# T07_411.net
KiCad netlist of a schematic drawn in EAGLE
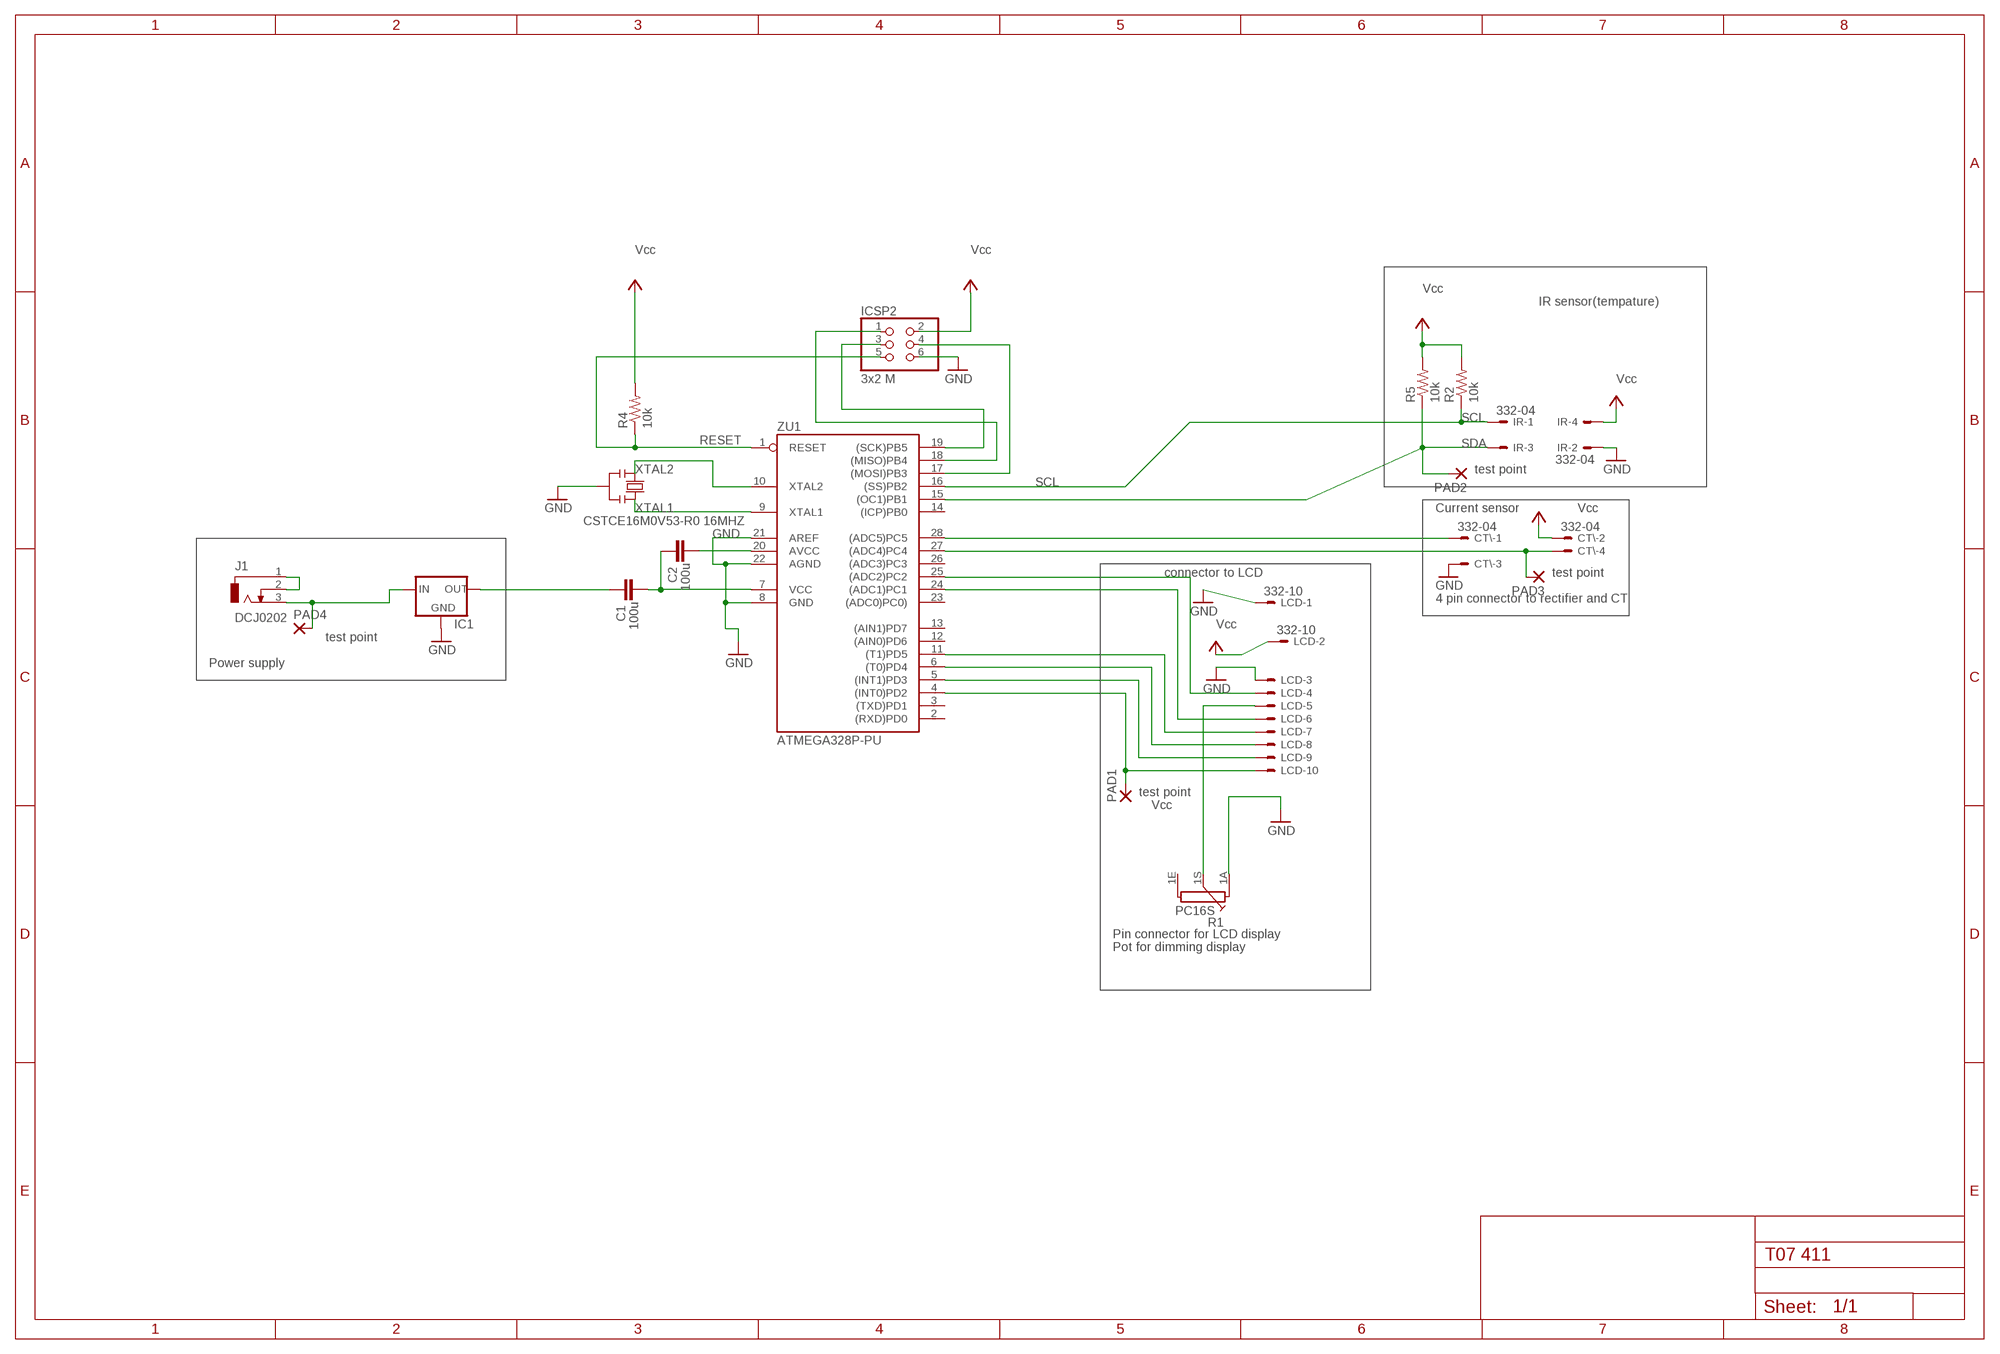
[diagram p0: schematic, sheet 1]

(export (version "E")
  (design (tool "Eeschema 10.0.6"))
  (components
    (comp (ref "C1")
      (value "100u")
      (footprint "eagle-import:C0603-ROUND")
      (libsource (lib "eagle-import") (part "C-EU0603-RND"))
    )
    (comp (ref "C2")
      (value "100u")
      (footprint "eagle-import:C0603-ROUND")
      (libsource (lib "eagle-import") (part "C-EU0603-RND"))
    )
    (comp (ref "CT\\")
      (value "332-04")
      (footprint "eagle-import:332-04")
      (libsource (lib "eagle-import") (part "332-04"))
    )
    (comp (ref "IC1")
      (value "78XXL")
      (footprint "eagle-import:78XXL")
      (libsource (lib "eagle-import") (part "78XXL"))
    )
    (comp (ref "ICSP2")
      (value "3x2 M")
      (footprint "eagle-import:2X03")
      (libsource (lib "eagle-import") (part "PINHD-2X3"))
    )
    (comp (ref "IR")
      (value "332-04")
      (footprint "eagle-import:332-04")
      (libsource (lib "eagle-import") (part "332-04"))
    )
    (comp (ref "J1")
      (value "DCJ0202")
      (footprint "eagle-import:DCJ0202")
      (libsource (lib "eagle-import") (part "DCJ0202"))
    )
    (comp (ref "LCD")
      (value "332-10")
      (footprint "eagle-import:332-10")
      (libsource (lib "eagle-import") (part "332-10"))
    )
    (comp (ref "PAD1")
      (value "1,6/0,9")
      (footprint "eagle-import:1,6_0,9")
      (libsource (lib "eagle-import") (part "1,6/0,9"))
    )
    (comp (ref "PAD2")
      (value "1,6/0,9")
      (footprint "eagle-import:1,6_0,9")
      (libsource (lib "eagle-import") (part "1,6/0,9"))
    )
    (comp (ref "PAD3")
      (value "1,6/0,9")
      (footprint "eagle-import:1,6_0,9")
      (libsource (lib "eagle-import") (part "1,6/0,9"))
    )
    (comp (ref "PAD4")
      (value "1,6/0,9")
      (footprint "eagle-import:1,6_0,9")
      (libsource (lib "eagle-import") (part "1,6/0,9"))
    )
    (comp (ref "R1")
      (value "PC16S")
      (footprint "eagle-import:PC16S")
      (libsource (lib "eagle-import") (part "PC16S"))
    )
    (comp (ref "R2")
      (value "10k")
      (footprint "eagle-import:0402-RES")
      (libsource (lib "eagle-import") (part "RESISTOR0402-RES"))
    )
    (comp (ref "R4")
      (value "10k")
      (footprint "eagle-import:0402-RES")
      (libsource (lib "eagle-import") (part "RESISTOR0402-RES"))
    )
    (comp (ref "R5")
      (value "10k")
      (footprint "eagle-import:0402-RES")
      (libsource (lib "eagle-import") (part "RESISTOR0402-RES"))
    )
    (comp (ref "Y3")
      (value "CSTCE16M0V53-R0 16MHZ")
      (footprint "eagle-import:RESONATOR")
      (libsource (lib "eagle-import") (part "RESONATORMU"))
    )
    (comp (ref "ZU1")
      (value "ATMEGA328P-PU")
      (footprint "eagle-import:DIL28-3")
      (libsource (lib "eagle-import") (part "ATMEGA328P-PU"))
    )
  )
  (nets
    (net (code "1") (name "+5V") (class "Default")
      (node (ref "CT\\") (pin "2") (pinfunction "S_2") (pintype "passive"))
      (node (ref "ICSP2") (pin "2") (pinfunction "2_2") (pintype "passive"))
      (node (ref "IR") (pin "4") (pinfunction "S_4") (pintype "passive"))
      (node (ref "LCD") (pin "2") (pinfunction "S_2") (pintype "passive"))
      (node (ref "R2") (pin "2") (pinfunction "2_2") (pintype "passive"))
      (node (ref "R4") (pin "2") (pinfunction "2_2") (pintype "passive"))
      (node (ref "R5") (pin "2") (pinfunction "2_2") (pintype "passive"))
    )
    (net (code "2") (name "/RESET") (class "Default")
      (node (ref "ICSP2") (pin "5") (pinfunction "5_5") (pintype "passive"))
      (node (ref "R4") (pin "1") (pinfunction "1_1") (pintype "passive"))
      (node (ref "ZU1") (pin "1") (pinfunction "RESET_1") (pintype "input"))
    )
    (net (code "3") (name "/SCL") (class "Default")
      (node (ref "IR") (pin "1") (pinfunction "S_1") (pintype "passive"))
      (node (ref "R2") (pin "1") (pinfunction "1_1") (pintype "passive"))
      (node (ref "ZU1") (pin "16") (pinfunction "(SS)PB2_16") (pintype "bidirectional"))
    )
    (net (code "4") (name "/SDA") (class "Default")
      (node (ref "IR") (pin "3") (pinfunction "S_3") (pintype "passive"))
      (node (ref "PAD2") (pin "1") (pinfunction "P_1") (pintype "passive"))
      (node (ref "R5") (pin "1") (pinfunction "1_1") (pintype "passive"))
      (node (ref "ZU1") (pin "15") (pinfunction "(OC1)PB1_15") (pintype "bidirectional"))
    )
    (net (code "5") (name "/XTAL1") (class "Default")
      (node (ref "Y3") (pin "3") (pinfunction "3_3") (pintype "passive"))
      (node (ref "ZU1") (pin "9") (pinfunction "XTAL1_9") (pintype "bidirectional"))
    )
    (net (code "6") (name "/XTAL2") (class "Default")
      (node (ref "Y3") (pin "1") (pinfunction "1_1") (pintype "passive"))
      (node (ref "ZU1") (pin "10") (pinfunction "XTAL2_10") (pintype "bidirectional"))
    )
    (net (code "7") (name "GND") (class "Default")
      (node (ref "CT\\") (pin "3") (pinfunction "S_3") (pintype "passive"))
      (node (ref "IC1") (pin "GND") (pinfunction "GND_GND") (pintype "input"))
      (node (ref "ICSP2") (pin "6") (pinfunction "6_6") (pintype "passive"))
      (node (ref "IR") (pin "2") (pinfunction "S_2") (pintype "passive"))
      (node (ref "LCD") (pin "1") (pinfunction "S_1") (pintype "passive"))
      (node (ref "LCD") (pin "3") (pinfunction "S_3") (pintype "passive"))
      (node (ref "R1") (pin "1A") (pinfunction "1A_1A") (pintype "passive"))
      (node (ref "Y3") (pin "2") (pinfunction "2_2") (pintype "passive"))
      (node (ref "ZU1") (pin "21") (pinfunction "AREF_21") (pintype "passive"))
      (node (ref "ZU1") (pin "22") (pinfunction "AGND_22") (pintype "power_in"))
      (node (ref "ZU1") (pin "8") (pinfunction "GND_8") (pintype "power_in"))
    )
    (net (code "8") (name "Net-(C1-Pad2)") (class "Default")
      (node (ref "C1") (pin "2") (pinfunction "2_2") (pintype "passive"))
      (node (ref "IC1") (pin "OUT") (pinfunction "OUT_OUT") (pintype "passive"))
    )
    (net (code "9") (name "Net-(CT\\A-S)") (class "Default")
      (node (ref "CT\\") (pin "1") (pinfunction "S_1") (pintype "passive"))
      (node (ref "ZU1") (pin "28") (pinfunction "(ADC5)PC5_28") (pintype "bidirectional"))
    )
    (net (code "10") (name "Net-(CT\\D-S)") (class "Default")
      (node (ref "CT\\") (pin "4") (pinfunction "S_4") (pintype "passive"))
      (node (ref "PAD3") (pin "1") (pinfunction "P_1") (pintype "passive"))
      (node (ref "ZU1") (pin "27") (pinfunction "(ADC4)PC4_27") (pintype "bidirectional"))
    )
    (net (code "11") (name "Net-(J1-Pad1)") (class "Default")
      (node (ref "J1") (pin "1") (pinfunction "1_1") (pintype "passive"))
      (node (ref "J1") (pin "2") (pinfunction "2_2") (pintype "passive"))
    )
    (net (code "12") (name "Net-(LCDB-S)") (class "Default")
      (node (ref "LCD") (pin "10") (pinfunction "S_10") (pintype "passive"))
      (node (ref "PAD1") (pin "1") (pinfunction "P_1") (pintype "passive"))
      (node (ref "ZU1") (pin "4") (pinfunction "(INT0)PD2_4") (pintype "bidirectional"))
    )
    (net (code "13") (name "Net-(LCDE-S)") (class "Default")
      (node (ref "LCD") (pin "4") (pinfunction "S_4") (pintype "passive"))
      (node (ref "ZU1") (pin "25") (pinfunction "(ADC2)PC2_25") (pintype "bidirectional"))
    )
    (net (code "14") (name "Net-(LCDF-S)") (class "Default")
      (node (ref "LCD") (pin "5") (pinfunction "S_5") (pintype "passive"))
      (node (ref "R1") (pin "1S") (pinfunction "1S_1S") (pintype "passive"))
    )
    (net (code "15") (name "Net-(LCDG-S)") (class "Default")
      (node (ref "LCD") (pin "6") (pinfunction "S_6") (pintype "passive"))
      (node (ref "ZU1") (pin "24") (pinfunction "(ADC1)PC1_24") (pintype "bidirectional"))
    )
    (net (code "16") (name "Net-(LCDH-S)") (class "Default")
      (node (ref "LCD") (pin "7") (pinfunction "S_7") (pintype "passive"))
      (node (ref "ZU1") (pin "11") (pinfunction "(T1)PD5_11") (pintype "bidirectional"))
    )
    (net (code "17") (name "Net-(LCDI-S)") (class "Default")
      (node (ref "LCD") (pin "8") (pinfunction "S_8") (pintype "passive"))
      (node (ref "ZU1") (pin "6") (pinfunction "(T0)PD4_6") (pintype "bidirectional"))
    )
    (net (code "18") (name "Net-(LCDJ-S)") (class "Default")
      (node (ref "LCD") (pin "9") (pinfunction "S_9") (pintype "passive"))
      (node (ref "ZU1") (pin "5") (pinfunction "(INT1)PD3_5") (pintype "bidirectional"))
    )
    (net (code "19") (name "Net-(PAD4-P)") (class "Default")
      (node (ref "IC1") (pin "IN") (pinfunction "IN_IN") (pintype "input"))
      (node (ref "J1") (pin "3") (pinfunction "3_3") (pintype "passive"))
      (node (ref "PAD4") (pin "1") (pinfunction "P_1") (pintype "passive"))
    )
    (net (code "20") (name "Net-(ZU1-(MISO)PB4)") (class "Default")
      (node (ref "ICSP2") (pin "1") (pinfunction "1_1") (pintype "passive"))
      (node (ref "ZU1") (pin "18") (pinfunction "(MISO)PB4_18") (pintype "bidirectional"))
    )
    (net (code "21") (name "Net-(ZU1-(MOSI)PB3)") (class "Default")
      (node (ref "ICSP2") (pin "4") (pinfunction "4_4") (pintype "passive"))
      (node (ref "ZU1") (pin "17") (pinfunction "(MOSI)PB3_17") (pintype "bidirectional"))
    )
    (net (code "22") (name "Net-(ZU1-(SCK)PB5)") (class "Default")
      (node (ref "ICSP2") (pin "3") (pinfunction "3_3") (pintype "passive"))
      (node (ref "ZU1") (pin "19") (pinfunction "(SCK)PB5_19") (pintype "bidirectional"))
    )
    (net (code "23") (name "Net-(ZU1-AVCC)") (class "Default")
      (node (ref "C2") (pin "1") (pinfunction "1_1") (pintype "passive"))
      (node (ref "ZU1") (pin "20") (pinfunction "AVCC_20") (pintype "power_in"))
    )
    (net (code "24") (name "Net-(ZU1-VCC)") (class "Default")
      (node (ref "C1") (pin "1") (pinfunction "1_1") (pintype "passive"))
      (node (ref "C2") (pin "2") (pinfunction "2_2") (pintype "passive"))
      (node (ref "ZU1") (pin "7") (pinfunction "VCC_7") (pintype "power_in"))
    )
    (net (code "25") (name "unconnected-(R1-Pad1E)") (class "Default")
      (node (ref "R1") (pin "1E") (pinfunction "1E_1E") (pintype "passive"))
    )
    (net (code "26") (name "unconnected-(ZU1-(ADC0)PC0)-Pad23)") (class "Default")
      (node (ref "ZU1") (pin "23") (pinfunction "(ADC0)PC0)_23") (pintype "bidirectional"))
    )
    (net (code "27") (name "unconnected-(ZU1-(ADC3)PC3-Pad26)") (class "Default")
      (node (ref "ZU1") (pin "26") (pinfunction "(ADC3)PC3_26") (pintype "bidirectional"))
    )
    (net (code "28") (name "unconnected-(ZU1-(AIN0)PD6-Pad12)") (class "Default")
      (node (ref "ZU1") (pin "12") (pinfunction "(AIN0)PD6_12") (pintype "bidirectional"))
    )
    (net (code "29") (name "unconnected-(ZU1-(AIN1)PD7-Pad13)") (class "Default")
      (node (ref "ZU1") (pin "13") (pinfunction "(AIN1)PD7_13") (pintype "bidirectional"))
    )
    (net (code "30") (name "unconnected-(ZU1-(ICP)PB0-Pad14)") (class "Default")
      (node (ref "ZU1") (pin "14") (pinfunction "(ICP)PB0_14") (pintype "bidirectional"))
    )
    (net (code "31") (name "unconnected-(ZU1-(RXD)PD0-Pad2)") (class "Default")
      (node (ref "ZU1") (pin "2") (pinfunction "(RXD)PD0_2") (pintype "bidirectional"))
    )
    (net (code "32") (name "unconnected-(ZU1-(TXD)PD1-Pad3)") (class "Default")
      (node (ref "ZU1") (pin "3") (pinfunction "(TXD)PD1_3") (pintype "bidirectional"))
    )
  )
)
